# 3_MCU.net
KiCad netlist of a schematic drawn in Altium Designer
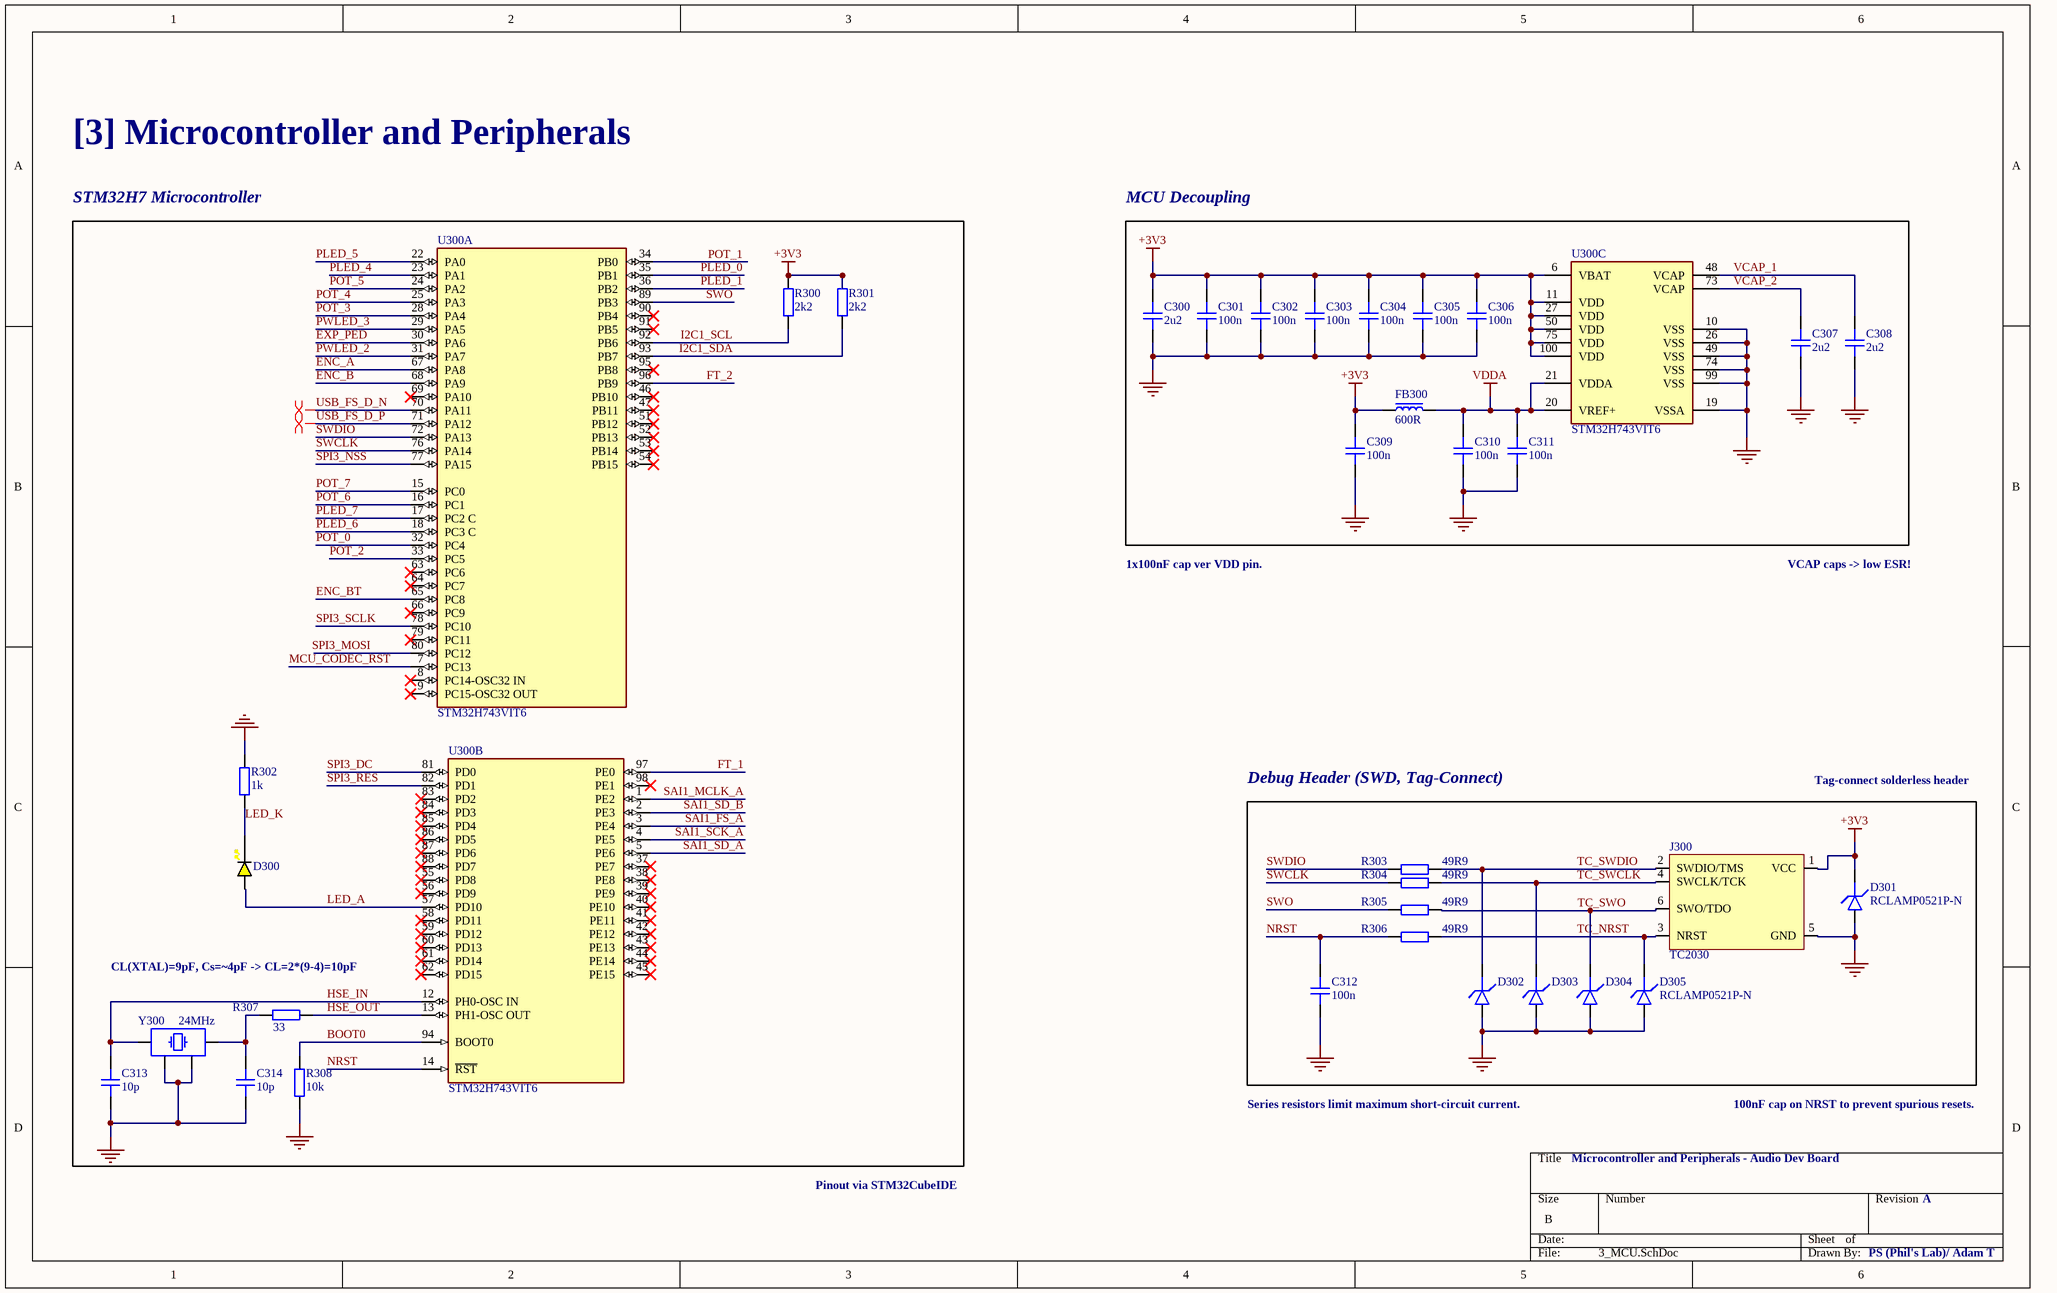
[diagram p0: 3_MCU.SchDoc]

(export (version "E")
  (design (tool "Eeschema 10.0.6"))
  (components
    (comp (ref "C300")
      (value "2u2")
      (footprint "CAP_0603")
      (description "Capacitor SMD 0603 16V")
      (libsource (lib "Schematic-Lib-PhilsLab") (part "CAP_0603_16V"))
    )
    (comp (ref "C301")
      (value "100n")
      (footprint "CAP_0402")
      (description "Capacitor SMD 0402")
      (libsource (lib "Schematic-Lib-PhilsLab") (part "CAP_0402"))
    )
    (comp (ref "C302")
      (value "100n")
      (footprint "CAP_0402")
      (description "Capacitor SMD 0402")
      (libsource (lib "Schematic-Lib-PhilsLab") (part "CAP_0402"))
    )
    (comp (ref "C303")
      (value "100n")
      (footprint "CAP_0402")
      (description "Capacitor SMD 0402")
      (libsource (lib "Schematic-Lib-PhilsLab") (part "CAP_0402"))
    )
    (comp (ref "C304")
      (value "100n")
      (footprint "CAP_0402")
      (description "Capacitor SMD 0402")
      (libsource (lib "Schematic-Lib-PhilsLab") (part "CAP_0402"))
    )
    (comp (ref "C305")
      (value "100n")
      (footprint "CAP_0402")
      (description "Capacitor SMD 0402")
      (libsource (lib "Schematic-Lib-PhilsLab") (part "CAP_0402"))
    )
    (comp (ref "C306")
      (value "100n")
      (footprint "CAP_0402")
      (description "Capacitor SMD 0402")
      (libsource (lib "Schematic-Lib-PhilsLab") (part "CAP_0402"))
    )
    (comp (ref "C307")
      (value "2u2")
      (footprint "CAP_0402")
      (description "Capacitor SMD 0402")
      (libsource (lib "Schematic-Lib-PhilsLab") (part "CAP_0402"))
    )
    (comp (ref "C308")
      (value "2u2")
      (footprint "CAP_0402")
      (description "Capacitor SMD 0402")
      (libsource (lib "Schematic-Lib-PhilsLab") (part "CAP_0402"))
    )
    (comp (ref "C309")
      (value "100n")
      (footprint "CAP_0402")
      (description "Capacitor SMD 0402")
      (libsource (lib "Schematic-Lib-PhilsLab") (part "CAP_0402"))
    )
    (comp (ref "C310")
      (value "100n")
      (footprint "CAP_0402")
      (description "Capacitor SMD 0402")
      (libsource (lib "Schematic-Lib-PhilsLab") (part "CAP_0402"))
    )
    (comp (ref "C311")
      (value "100n")
      (footprint "CAP_0402")
      (description "Capacitor SMD 0402")
      (libsource (lib "Schematic-Lib-PhilsLab") (part "CAP_0402"))
    )
    (comp (ref "C312")
      (value "100n")
      (footprint "CAP_0402")
      (description "Capacitor SMD 0402")
      (libsource (lib "Schematic-Lib-PhilsLab") (part "CAP_0402"))
    )
    (comp (ref "C313")
      (value "10p")
      (footprint "CAP_0402")
      (description "Capacitor SMD 0402 16V")
      (libsource (lib "Schematic-Lib-PhilsLab") (part "CAP_0402_16V"))
    )
    (comp (ref "C314")
      (value "10p")
      (footprint "CAP_0402")
      (description "Capacitor SMD 0402 16V")
      (libsource (lib "Schematic-Lib-PhilsLab") (part "CAP_0402_16V"))
    )
    (comp (ref "D300")
      (value "YELLOW")
      (footprint "LED_0402_YELLOW")
      (description "LED 0402 YELLOW SMD")
      (libsource (lib "Schematic-Lib-PhilsLab") (part "LED_0402_YELLOW"))
    )
    (comp (ref "D301")
      (value "RCLAMP0521P-N")
      (footprint "D_0402")
      (description "Diode TVS / ESD 0402")
      (libsource (lib "Schematic-Lib-PhilsLab") (part "D_TVS_0402"))
    )
    (comp (ref "D302")
      (value "RCLAMP0521P-N")
      (footprint "D_0402")
      (description "Diode TVS / ESD 0402")
      (libsource (lib "Schematic-Lib-PhilsLab") (part "D_TVS_0402"))
    )
    (comp (ref "D303")
      (value "RCLAMP0521P-N")
      (footprint "D_0402")
      (description "Diode TVS / ESD 0402")
      (libsource (lib "Schematic-Lib-PhilsLab") (part "D_TVS_0402"))
    )
    (comp (ref "D304")
      (value "RCLAMP0521P-N")
      (footprint "D_0402")
      (description "Diode TVS / ESD 0402")
      (libsource (lib "Schematic-Lib-PhilsLab") (part "D_TVS_0402"))
    )
    (comp (ref "D305")
      (value "RCLAMP0521P-N")
      (footprint "D_0402")
      (description "Diode TVS / ESD 0402")
      (libsource (lib "Schematic-Lib-PhilsLab") (part "D_TVS_0402"))
    )
    (comp (ref "FB300")
      (value "600R")
      (footprint "FB_0805")
      (description "Ferrite Bead SMD 0805 C2982098")
      (libsource (lib "Schematic-Lib-PhilsLab") (part "FB_0805"))
    )
    (comp (ref "J300")
      (value "TC2030")
      (footprint "TC2030-FP")
      (description "Tag-Connect No-Solder SWD Debug Connector DO NOT PLACE")
      (fields (field (name "MANUFACTURER") "Tag-Connect"))
      (libsource (lib "Schematic-Lib-PhilsLab") (part "TC2030"))
    )
    (comp (ref "R300")
      (value "2k2")
      (footprint "RES_0402")
      (description "Resistor SMD 0402")
      (libsource (lib "Schematic-Lib-PhilsLab") (part "RES_0402"))
    )
    (comp (ref "R301")
      (value "2k2")
      (footprint "RES_0402")
      (description "Resistor SMD 0402")
      (libsource (lib "Schematic-Lib-PhilsLab") (part "RES_0402"))
    )
    (comp (ref "R302")
      (value "1k")
      (footprint "RES_0402")
      (description "Resistor SMD 0402")
      (libsource (lib "Schematic-Lib-PhilsLab") (part "RES_0402"))
    )
    (comp (ref "R303")
      (value "49R9")
      (footprint "RES_0402")
      (description "Resistor SMD 0402")
      (libsource (lib "Schematic-Lib-PhilsLab") (part "RES_0402"))
    )
    (comp (ref "R304")
      (value "49R9")
      (footprint "RES_0402")
      (description "Resistor SMD 0402")
      (libsource (lib "Schematic-Lib-PhilsLab") (part "RES_0402"))
    )
    (comp (ref "R305")
      (value "49R9")
      (footprint "RES_0402")
      (description "Resistor SMD 0402")
      (libsource (lib "Schematic-Lib-PhilsLab") (part "RES_0402"))
    )
    (comp (ref "R306")
      (value "49R9")
      (footprint "RES_0402")
      (description "Resistor SMD 0402")
      (libsource (lib "Schematic-Lib-PhilsLab") (part "RES_0402"))
    )
    (comp (ref "R307")
      (value "33")
      (footprint "RES_0402")
      (description "Resistor SMD 0402")
      (libsource (lib "Schematic-Lib-PhilsLab") (part "RES_0402"))
    )
    (comp (ref "R308")
      (value "10k")
      (footprint "RES_0402")
      (description "Resistor SMD 0402")
      (libsource (lib "Schematic-Lib-PhilsLab") (part "RES_0402"))
    )
    (comp (ref "U300")
      (value "STM32H743VIT6")
      (footprint "FP-LQFP100-1L-MFG")
      (description "IC MCU 32BIT 2MB FLASH 100LQFP")
      (fields
        (field (name "OCTOPART") "https://octopart.com/stm32h743vit6-stmicroelectronics-76372527")
        (field (name "MANUFACTURER") "STMicroelectronics")
      )
      (libsource (lib "Altium Content Vault") (part "01082ce2885d1d16a22823c45526fe6"))
    )
    (comp (ref "Y300")
      (value "24MHz")
      (footprint "XTAL_3225")
      (description "Crystal SMD 24MHz 10PPM 7pF 3225")
      (fields (field (name "MANUFACTURER") "Epson"))
      (libsource (lib "Schematic-Lib-PhilsLab") (part "TSX-3225_24.0000MF15X-AC"))
    )
  )
  (nets
    (net (code "1") (name "+3V3") (class "Default")
      (node (ref "C300") (pin "2") (pinfunction "2_2") (pintype "passive"))
      (node (ref "C301") (pin "2") (pinfunction "2_2") (pintype "passive"))
      (node (ref "C302") (pin "2") (pinfunction "2_2") (pintype "passive"))
      (node (ref "C303") (pin "2") (pinfunction "2_2") (pintype "passive"))
      (node (ref "C304") (pin "2") (pinfunction "2_2") (pintype "passive"))
      (node (ref "C305") (pin "2") (pinfunction "2_2") (pintype "passive"))
      (node (ref "C306") (pin "2") (pinfunction "2_2") (pintype "passive"))
      (node (ref "C309") (pin "2") (pinfunction "2_2") (pintype "passive"))
      (node (ref "D301") (pin "K") (pinfunction "K_K") (pintype "passive"))
      (node (ref "FB300") (pin "1") (pinfunction "1_1") (pintype "passive"))
      (node (ref "J300") (pin "1") (pinfunction "VCC_1") (pintype "passive"))
      (node (ref "R300") (pin "2") (pinfunction "2_2") (pintype "passive"))
      (node (ref "R301") (pin "2") (pinfunction "2_2") (pintype "passive"))
      (node (ref "U300") (pin "100") (pinfunction "VDD_100") (pintype "power_in"))
      (node (ref "U300") (pin "11") (pinfunction "VDD_11") (pintype "power_in"))
      (node (ref "U300") (pin "27") (pinfunction "VDD_27") (pintype "power_in"))
      (node (ref "U300") (pin "50") (pinfunction "VDD_50") (pintype "power_in"))
      (node (ref "U300") (pin "6") (pinfunction "VBAT_6") (pintype "power_in"))
      (node (ref "U300") (pin "75") (pinfunction "VDD_75") (pintype "power_in"))
    )
    (net (code "2") (name "/BOOT0") (class "Default")
      (node (ref "R308") (pin "2") (pinfunction "2_2") (pintype "passive"))
      (node (ref "U300") (pin "94") (pinfunction "BOOT0_94") (pintype "input"))
    )
    (net (code "3") (name "/ENC_A") (class "Default")
      (node (ref "U300") (pin "67") (pinfunction "PA8_67") (pintype "bidirectional"))
    )
    (net (code "4") (name "/ENC_B") (class "Default")
      (node (ref "U300") (pin "68") (pinfunction "PA9_68") (pintype "bidirectional"))
    )
    (net (code "5") (name "/ENC_BT") (class "Default")
      (node (ref "U300") (pin "65") (pinfunction "PC8_65") (pintype "bidirectional"))
    )
    (net (code "6") (name "/EXP_PED") (class "Default")
      (node (ref "U300") (pin "30") (pinfunction "PA6_30") (pintype "bidirectional"))
    )
    (net (code "7") (name "/FT_1") (class "Default")
      (node (ref "U300") (pin "97") (pinfunction "PE0_97") (pintype "bidirectional"))
    )
    (net (code "8") (name "/FT_2") (class "Default")
      (node (ref "U300") (pin "96") (pinfunction "PB9_96") (pintype "bidirectional"))
    )
    (net (code "9") (name "/HSE_IN") (class "Default")
      (node (ref "C313") (pin "2") (pinfunction "2_2") (pintype "passive"))
      (node (ref "U300") (pin "12") (pinfunction "PH0-OSC_IN_12") (pintype "bidirectional"))
      (node (ref "Y300") (pin "1") (pinfunction "1_1") (pintype "passive"))
    )
    (net (code "10") (name "/HSE_OUT") (class "Default")
      (node (ref "R307") (pin "2") (pinfunction "2_2") (pintype "passive"))
      (node (ref "U300") (pin "13") (pinfunction "PH1-OSC_OUT_13") (pintype "bidirectional"))
    )
    (net (code "11") (name "/I2C1_SCL") (class "Default")
      (node (ref "R300") (pin "1") (pinfunction "1_1") (pintype "passive"))
      (node (ref "U300") (pin "92") (pinfunction "PB6_92") (pintype "bidirectional"))
    )
    (net (code "12") (name "/I2C1_SDA") (class "Default")
      (node (ref "R301") (pin "1") (pinfunction "1_1") (pintype "passive"))
      (node (ref "U300") (pin "93") (pinfunction "PB7_93") (pintype "bidirectional"))
    )
    (net (code "13") (name "/LED_A") (class "Default")
      (node (ref "D300") (pin "A") (pinfunction "A_A") (pintype "passive"))
      (node (ref "U300") (pin "57") (pinfunction "PD10_57") (pintype "bidirectional"))
    )
    (net (code "14") (name "/LED_K") (class "Default")
      (node (ref "D300") (pin "K") (pinfunction "K_K") (pintype "passive"))
      (node (ref "R302") (pin "2") (pinfunction "2_2") (pintype "passive"))
    )
    (net (code "15") (name "/MCU_CODEC_RST") (class "Default")
      (node (ref "U300") (pin "7") (pinfunction "PC13_7") (pintype "bidirectional"))
    )
    (net (code "16") (name "/NRST") (class "Default")
      (node (ref "C312") (pin "2") (pinfunction "2_2") (pintype "passive"))
      (node (ref "R306") (pin "1") (pinfunction "1_1") (pintype "passive"))
      (node (ref "U300") (pin "14") (pinfunction "~{RST}_14") (pintype "input"))
    )
    (net (code "17") (name "/PLED_0") (class "Default")
      (node (ref "U300") (pin "35") (pinfunction "PB1_35") (pintype "bidirectional"))
    )
    (net (code "18") (name "/PLED_1") (class "Default")
      (node (ref "U300") (pin "36") (pinfunction "PB2_36") (pintype "bidirectional"))
    )
    (net (code "19") (name "/PLED_4") (class "Default")
      (node (ref "U300") (pin "23") (pinfunction "PA1_23") (pintype "bidirectional"))
    )
    (net (code "20") (name "/PLED_5") (class "Default")
      (node (ref "U300") (pin "22") (pinfunction "PA0_22") (pintype "bidirectional"))
    )
    (net (code "21") (name "/PLED_6") (class "Default")
      (node (ref "U300") (pin "18") (pinfunction "PC3_C_18") (pintype "bidirectional"))
    )
    (net (code "22") (name "/PLED_7") (class "Default")
      (node (ref "U300") (pin "17") (pinfunction "PC2_C_17") (pintype "bidirectional"))
    )
    (net (code "23") (name "/POT_0") (class "Default")
      (node (ref "U300") (pin "32") (pinfunction "PC4_32") (pintype "bidirectional"))
    )
    (net (code "24") (name "/POT_1") (class "Default")
      (node (ref "U300") (pin "34") (pinfunction "PB0_34") (pintype "bidirectional"))
    )
    (net (code "25") (name "/POT_2") (class "Default")
      (node (ref "U300") (pin "33") (pinfunction "PC5_33") (pintype "bidirectional"))
    )
    (net (code "26") (name "/POT_3") (class "Default")
      (node (ref "U300") (pin "28") (pinfunction "PA4_28") (pintype "bidirectional"))
    )
    (net (code "27") (name "/POT_4") (class "Default")
      (node (ref "U300") (pin "25") (pinfunction "PA3_25") (pintype "bidirectional"))
    )
    (net (code "28") (name "/POT_5") (class "Default")
      (node (ref "U300") (pin "24") (pinfunction "PA2_24") (pintype "bidirectional"))
    )
    (net (code "29") (name "/POT_6") (class "Default")
      (node (ref "U300") (pin "16") (pinfunction "PC1_16") (pintype "bidirectional"))
    )
    (net (code "30") (name "/POT_7") (class "Default")
      (node (ref "U300") (pin "15") (pinfunction "PC0_15") (pintype "bidirectional"))
    )
    (net (code "31") (name "/PWLED_2") (class "Default")
      (node (ref "U300") (pin "31") (pinfunction "PA7_31") (pintype "bidirectional"))
    )
    (net (code "32") (name "/PWLED_3") (class "Default")
      (node (ref "U300") (pin "29") (pinfunction "PA5_29") (pintype "bidirectional"))
    )
    (net (code "33") (name "/SAI1_FS_A") (class "Default")
      (node (ref "U300") (pin "3") (pinfunction "PE4_3") (pintype "bidirectional"))
    )
    (net (code "34") (name "/SAI1_MCLK_A") (class "Default")
      (node (ref "U300") (pin "1") (pinfunction "PE2_1") (pintype "bidirectional"))
    )
    (net (code "35") (name "/SAI1_SCK_A") (class "Default")
      (node (ref "U300") (pin "4") (pinfunction "PE5_4") (pintype "bidirectional"))
    )
    (net (code "36") (name "/SAI1_SD_A") (class "Default")
      (node (ref "U300") (pin "5") (pinfunction "PE6_5") (pintype "bidirectional"))
    )
    (net (code "37") (name "/SAI1_SD_B") (class "Default")
      (node (ref "U300") (pin "2") (pinfunction "PE3_2") (pintype "bidirectional"))
    )
    (net (code "38") (name "/SPI3_DC") (class "Default")
      (node (ref "U300") (pin "81") (pinfunction "PD0_81") (pintype "bidirectional"))
    )
    (net (code "39") (name "/SPI3_MOSI") (class "Default")
      (node (ref "U300") (pin "80") (pinfunction "PC12_80") (pintype "bidirectional"))
    )
    (net (code "40") (name "/SPI3_NSS") (class "Default")
      (node (ref "U300") (pin "77") (pinfunction "PA15_77") (pintype "bidirectional"))
    )
    (net (code "41") (name "/SPI3_RES") (class "Default")
      (node (ref "U300") (pin "82") (pinfunction "PD1_82") (pintype "bidirectional"))
    )
    (net (code "42") (name "/SPI3_SCLK") (class "Default")
      (node (ref "U300") (pin "78") (pinfunction "PC10_78") (pintype "bidirectional"))
    )
    (net (code "43") (name "/SWCLK") (class "Default")
      (node (ref "R304") (pin "1") (pinfunction "1_1") (pintype "passive"))
      (node (ref "U300") (pin "76") (pinfunction "PA14_76") (pintype "bidirectional"))
    )
    (net (code "44") (name "/SWDIO") (class "Default")
      (node (ref "R303") (pin "1") (pinfunction "1_1") (pintype "passive"))
      (node (ref "U300") (pin "72") (pinfunction "PA13_72") (pintype "bidirectional"))
    )
    (net (code "45") (name "/SWO") (class "Default")
      (node (ref "R305") (pin "1") (pinfunction "1_1") (pintype "passive"))
      (node (ref "U300") (pin "89") (pinfunction "PB3_89") (pintype "bidirectional"))
    )
    (net (code "46") (name "/TC_NRST") (class "Default")
      (node (ref "D305") (pin "K") (pinfunction "K_K") (pintype "passive"))
      (node (ref "J300") (pin "3") (pinfunction "NRST_3") (pintype "passive"))
      (node (ref "R306") (pin "2") (pinfunction "2_2") (pintype "passive"))
    )
    (net (code "47") (name "/TC_SWCLK") (class "Default")
      (node (ref "D303") (pin "K") (pinfunction "K_K") (pintype "passive"))
      (node (ref "J300") (pin "4") (pinfunction "SWCLK/TCK_4") (pintype "passive"))
      (node (ref "R304") (pin "2") (pinfunction "2_2") (pintype "passive"))
    )
    (net (code "48") (name "/TC_SWDIO") (class "Default")
      (node (ref "D302") (pin "K") (pinfunction "K_K") (pintype "passive"))
      (node (ref "J300") (pin "2") (pinfunction "SWDIO/TMS_2") (pintype "passive"))
      (node (ref "R303") (pin "2") (pinfunction "2_2") (pintype "passive"))
    )
    (net (code "49") (name "/TC_SWO") (class "Default")
      (node (ref "D304") (pin "K") (pinfunction "K_K") (pintype "passive"))
      (node (ref "J300") (pin "6") (pinfunction "SWO/TDO_6") (pintype "passive"))
      (node (ref "R305") (pin "2") (pinfunction "2_2") (pintype "passive"))
    )
    (net (code "50") (name "/USB_FS_D_N") (class "Default")
      (node (ref "U300") (pin "70") (pinfunction "PA11_70") (pintype "bidirectional"))
    )
    (net (code "51") (name "/USB_FS_D_P") (class "Default")
      (node (ref "U300") (pin "71") (pinfunction "PA12_71") (pintype "bidirectional"))
    )
    (net (code "52") (name "/VCAP_1") (class "Default")
      (node (ref "C308") (pin "2") (pinfunction "2_2") (pintype "passive"))
      (node (ref "U300") (pin "48") (pinfunction "VCAP_48") (pintype "passive"))
    )
    (net (code "53") (name "/VCAP_2") (class "Default")
      (node (ref "C307") (pin "2") (pinfunction "2_2") (pintype "passive"))
      (node (ref "U300") (pin "73") (pinfunction "VCAP_73") (pintype "passive"))
    )
    (net (code "54") (name "GND") (class "Default")
      (node (ref "C300") (pin "1") (pinfunction "1_1") (pintype "passive"))
      (node (ref "C301") (pin "1") (pinfunction "1_1") (pintype "passive"))
      (node (ref "C302") (pin "1") (pinfunction "1_1") (pintype "passive"))
      (node (ref "C303") (pin "1") (pinfunction "1_1") (pintype "passive"))
      (node (ref "C304") (pin "1") (pinfunction "1_1") (pintype "passive"))
      (node (ref "C305") (pin "1") (pinfunction "1_1") (pintype "passive"))
      (node (ref "C306") (pin "1") (pinfunction "1_1") (pintype "passive"))
      (node (ref "C307") (pin "1") (pinfunction "1_1") (pintype "passive"))
      (node (ref "C308") (pin "1") (pinfunction "1_1") (pintype "passive"))
      (node (ref "C309") (pin "1") (pinfunction "1_1") (pintype "passive"))
      (node (ref "C310") (pin "1") (pinfunction "1_1") (pintype "passive"))
      (node (ref "C311") (pin "1") (pinfunction "1_1") (pintype "passive"))
      (node (ref "C312") (pin "1") (pinfunction "1_1") (pintype "passive"))
      (node (ref "C313") (pin "1") (pinfunction "1_1") (pintype "passive"))
      (node (ref "C314") (pin "1") (pinfunction "1_1") (pintype "passive"))
      (node (ref "D301") (pin "A") (pinfunction "A_A") (pintype "passive"))
      (node (ref "D302") (pin "A") (pinfunction "A_A") (pintype "passive"))
      (node (ref "D303") (pin "A") (pinfunction "A_A") (pintype "passive"))
      (node (ref "D304") (pin "A") (pinfunction "A_A") (pintype "passive"))
      (node (ref "D305") (pin "A") (pinfunction "A_A") (pintype "passive"))
      (node (ref "J300") (pin "5") (pinfunction "GND_5") (pintype "passive"))
      (node (ref "R302") (pin "1") (pinfunction "1_1") (pintype "passive"))
      (node (ref "R308") (pin "1") (pinfunction "1_1") (pintype "passive"))
      (node (ref "U300") (pin "10") (pinfunction "VSS_10") (pintype "power_in"))
      (node (ref "U300") (pin "19") (pinfunction "VSSA_19") (pintype "power_in"))
      (node (ref "U300") (pin "26") (pinfunction "VSS_26") (pintype "power_in"))
      (node (ref "U300") (pin "49") (pinfunction "VSS_49") (pintype "power_in"))
      (node (ref "U300") (pin "74") (pinfunction "VSS_74") (pintype "power_in"))
      (node (ref "U300") (pin "99") (pinfunction "VSS_99") (pintype "power_in"))
      (node (ref "Y300") (pin "2") (pinfunction "2_2") (pintype "passive"))
      (node (ref "Y300") (pin "4") (pinfunction "4_4") (pintype "passive"))
    )
    (net (code "55") (name "Net-(C314-Pad2)") (class "Default")
      (node (ref "C314") (pin "2") (pinfunction "2_2") (pintype "passive"))
      (node (ref "R307") (pin "1") (pinfunction "1_1") (pintype "passive"))
      (node (ref "Y300") (pin "3") (pinfunction "3_3") (pintype "passive"))
    )
    (net (code "56") (name "VDDA") (class "Default")
      (node (ref "C310") (pin "2") (pinfunction "2_2") (pintype "passive"))
      (node (ref "C311") (pin "2") (pinfunction "2_2") (pintype "passive"))
      (node (ref "FB300") (pin "2") (pinfunction "2_2") (pintype "passive"))
      (node (ref "U300") (pin "20") (pinfunction "VREF+_20") (pintype "power_in"))
      (node (ref "U300") (pin "21") (pinfunction "VDDA_21") (pintype "power_in"))
    )
    (net (code "57") (name "unconnected-(U300A-PA10-Pad69)") (class "Default")
      (node (ref "U300") (pin "69") (pinfunction "PA10_69") (pintype "bidirectional+no_connect"))
    )
    (net (code "58") (name "unconnected-(U300A-PB4-Pad90)") (class "Default")
      (node (ref "U300") (pin "90") (pinfunction "PB4_90") (pintype "bidirectional+no_connect"))
    )
    (net (code "59") (name "unconnected-(U300A-PB5-Pad91)") (class "Default")
      (node (ref "U300") (pin "91") (pinfunction "PB5_91") (pintype "bidirectional+no_connect"))
    )
    (net (code "60") (name "unconnected-(U300A-PB8-Pad95)") (class "Default")
      (node (ref "U300") (pin "95") (pinfunction "PB8_95") (pintype "bidirectional+no_connect"))
    )
    (net (code "61") (name "unconnected-(U300A-PB10-Pad46)") (class "Default")
      (node (ref "U300") (pin "46") (pinfunction "PB10_46") (pintype "bidirectional+no_connect"))
    )
    (net (code "62") (name "unconnected-(U300A-PB11-Pad47)") (class "Default")
      (node (ref "U300") (pin "47") (pinfunction "PB11_47") (pintype "bidirectional+no_connect"))
    )
    (net (code "63") (name "unconnected-(U300A-PB12-Pad51)") (class "Default")
      (node (ref "U300") (pin "51") (pinfunction "PB12_51") (pintype "bidirectional+no_connect"))
    )
    (net (code "64") (name "unconnected-(U300A-PB13-Pad52)") (class "Default")
      (node (ref "U300") (pin "52") (pinfunction "PB13_52") (pintype "bidirectional+no_connect"))
    )
    (net (code "65") (name "unconnected-(U300A-PB14-Pad53)") (class "Default")
      (node (ref "U300") (pin "53") (pinfunction "PB14_53") (pintype "bidirectional+no_connect"))
    )
    (net (code "66") (name "unconnected-(U300A-PB15-Pad54)") (class "Default")
      (node (ref "U300") (pin "54") (pinfunction "PB15_54") (pintype "bidirectional+no_connect"))
    )
    (net (code "67") (name "unconnected-(U300A-PC6-Pad63)") (class "Default")
      (node (ref "U300") (pin "63") (pinfunction "PC6_63") (pintype "bidirectional+no_connect"))
    )
    (net (code "68") (name "unconnected-(U300A-PC7-Pad64)") (class "Default")
      (node (ref "U300") (pin "64") (pinfunction "PC7_64") (pintype "bidirectional+no_connect"))
    )
    (net (code "69") (name "unconnected-(U300A-PC9-Pad66)") (class "Default")
      (node (ref "U300") (pin "66") (pinfunction "PC9_66") (pintype "bidirectional+no_connect"))
    )
    (net (code "70") (name "unconnected-(U300A-PC11-Pad79)") (class "Default")
      (node (ref "U300") (pin "79") (pinfunction "PC11_79") (pintype "bidirectional+no_connect"))
    )
    (net (code "71") (name "unconnected-(U300A-PC14-OSC32_IN-Pad8)") (class "Default")
      (node (ref "U300") (pin "8") (pinfunction "PC14-OSC32_IN_8") (pintype "bidirectional+no_connect"))
    )
    (net (code "72") (name "unconnected-(U300A-PC15-OSC32_OUT-Pad9)") (class "Default")
      (node (ref "U300") (pin "9") (pinfunction "PC15-OSC32_OUT_9") (pintype "bidirectional+no_connect"))
    )
    (net (code "73") (name "unconnected-(U300B-PD2-Pad83)") (class "Default")
      (node (ref "U300") (pin "83") (pinfunction "PD2_83") (pintype "bidirectional+no_connect"))
    )
    (net (code "74") (name "unconnected-(U300B-PD3-Pad84)") (class "Default")
      (node (ref "U300") (pin "84") (pinfunction "PD3_84") (pintype "bidirectional+no_connect"))
    )
    (net (code "75") (name "unconnected-(U300B-PD4-Pad85)") (class "Default")
      (node (ref "U300") (pin "85") (pinfunction "PD4_85") (pintype "bidirectional+no_connect"))
    )
    (net (code "76") (name "unconnected-(U300B-PD5-Pad86)") (class "Default")
      (node (ref "U300") (pin "86") (pinfunction "PD5_86") (pintype "bidirectional+no_connect"))
    )
    (net (code "77") (name "unconnected-(U300B-PD6-Pad87)") (class "Default")
      (node (ref "U300") (pin "87") (pinfunction "PD6_87") (pintype "bidirectional+no_connect"))
    )
    (net (code "78") (name "unconnected-(U300B-PD7-Pad88)") (class "Default")
      (node (ref "U300") (pin "88") (pinfunction "PD7_88") (pintype "bidirectional+no_connect"))
    )
    (net (code "79") (name "unconnected-(U300B-PD8-Pad55)") (class "Default")
      (node (ref "U300") (pin "55") (pinfunction "PD8_55") (pintype "bidirectional+no_connect"))
    )
    (net (code "80") (name "unconnected-(U300B-PD9-Pad56)") (class "Default")
      (node (ref "U300") (pin "56") (pinfunction "PD9_56") (pintype "bidirectional+no_connect"))
    )
    (net (code "81") (name "unconnected-(U300B-PD11-Pad58)") (class "Default")
      (node (ref "U300") (pin "58") (pinfunction "PD11_58") (pintype "bidirectional+no_connect"))
    )
    (net (code "82") (name "unconnected-(U300B-PD12-Pad59)") (class "Default")
      (node (ref "U300") (pin "59") (pinfunction "PD12_59") (pintype "bidirectional+no_connect"))
    )
    (net (code "83") (name "unconnected-(U300B-PD13-Pad60)") (class "Default")
      (node (ref "U300") (pin "60") (pinfunction "PD13_60") (pintype "bidirectional+no_connect"))
    )
    (net (code "84") (name "unconnected-(U300B-PD14-Pad61)") (class "Default")
      (node (ref "U300") (pin "61") (pinfunction "PD14_61") (pintype "bidirectional+no_connect"))
    )
    (net (code "85") (name "unconnected-(U300B-PD15-Pad62)") (class "Default")
      (node (ref "U300") (pin "62") (pinfunction "PD15_62") (pintype "bidirectional+no_connect"))
    )
    (net (code "86") (name "unconnected-(U300B-PE1-Pad98)") (class "Default")
      (node (ref "U300") (pin "98") (pinfunction "PE1_98") (pintype "bidirectional+no_connect"))
    )
    (net (code "87") (name "unconnected-(U300B-PE7-Pad37)") (class "Default")
      (node (ref "U300") (pin "37") (pinfunction "PE7_37") (pintype "bidirectional+no_connect"))
    )
    (net (code "88") (name "unconnected-(U300B-PE8-Pad38)") (class "Default")
      (node (ref "U300") (pin "38") (pinfunction "PE8_38") (pintype "bidirectional+no_connect"))
    )
    (net (code "89") (name "unconnected-(U300B-PE9-Pad39)") (class "Default")
      (node (ref "U300") (pin "39") (pinfunction "PE9_39") (pintype "bidirectional+no_connect"))
    )
    (net (code "90") (name "unconnected-(U300B-PE10-Pad40)") (class "Default")
      (node (ref "U300") (pin "40") (pinfunction "PE10_40") (pintype "bidirectional+no_connect"))
    )
    (net (code "91") (name "unconnected-(U300B-PE11-Pad41)") (class "Default")
      (node (ref "U300") (pin "41") (pinfunction "PE11_41") (pintype "bidirectional+no_connect"))
    )
    (net (code "92") (name "unconnected-(U300B-PE12-Pad42)") (class "Default")
      (node (ref "U300") (pin "42") (pinfunction "PE12_42") (pintype "bidirectional+no_connect"))
    )
    (net (code "93") (name "unconnected-(U300B-PE13-Pad43)") (class "Default")
      (node (ref "U300") (pin "43") (pinfunction "PE13_43") (pintype "bidirectional+no_connect"))
    )
    (net (code "94") (name "unconnected-(U300B-PE14-Pad44)") (class "Default")
      (node (ref "U300") (pin "44") (pinfunction "PE14_44") (pintype "bidirectional+no_connect"))
    )
    (net (code "95") (name "unconnected-(U300B-PE15-Pad45)") (class "Default")
      (node (ref "U300") (pin "45") (pinfunction "PE15_45") (pintype "bidirectional+no_connect"))
    )
  )
)
